# 10-ZYNQ_PWR_GND.net
KiCad netlist of a schematic drawn in Altium Designer
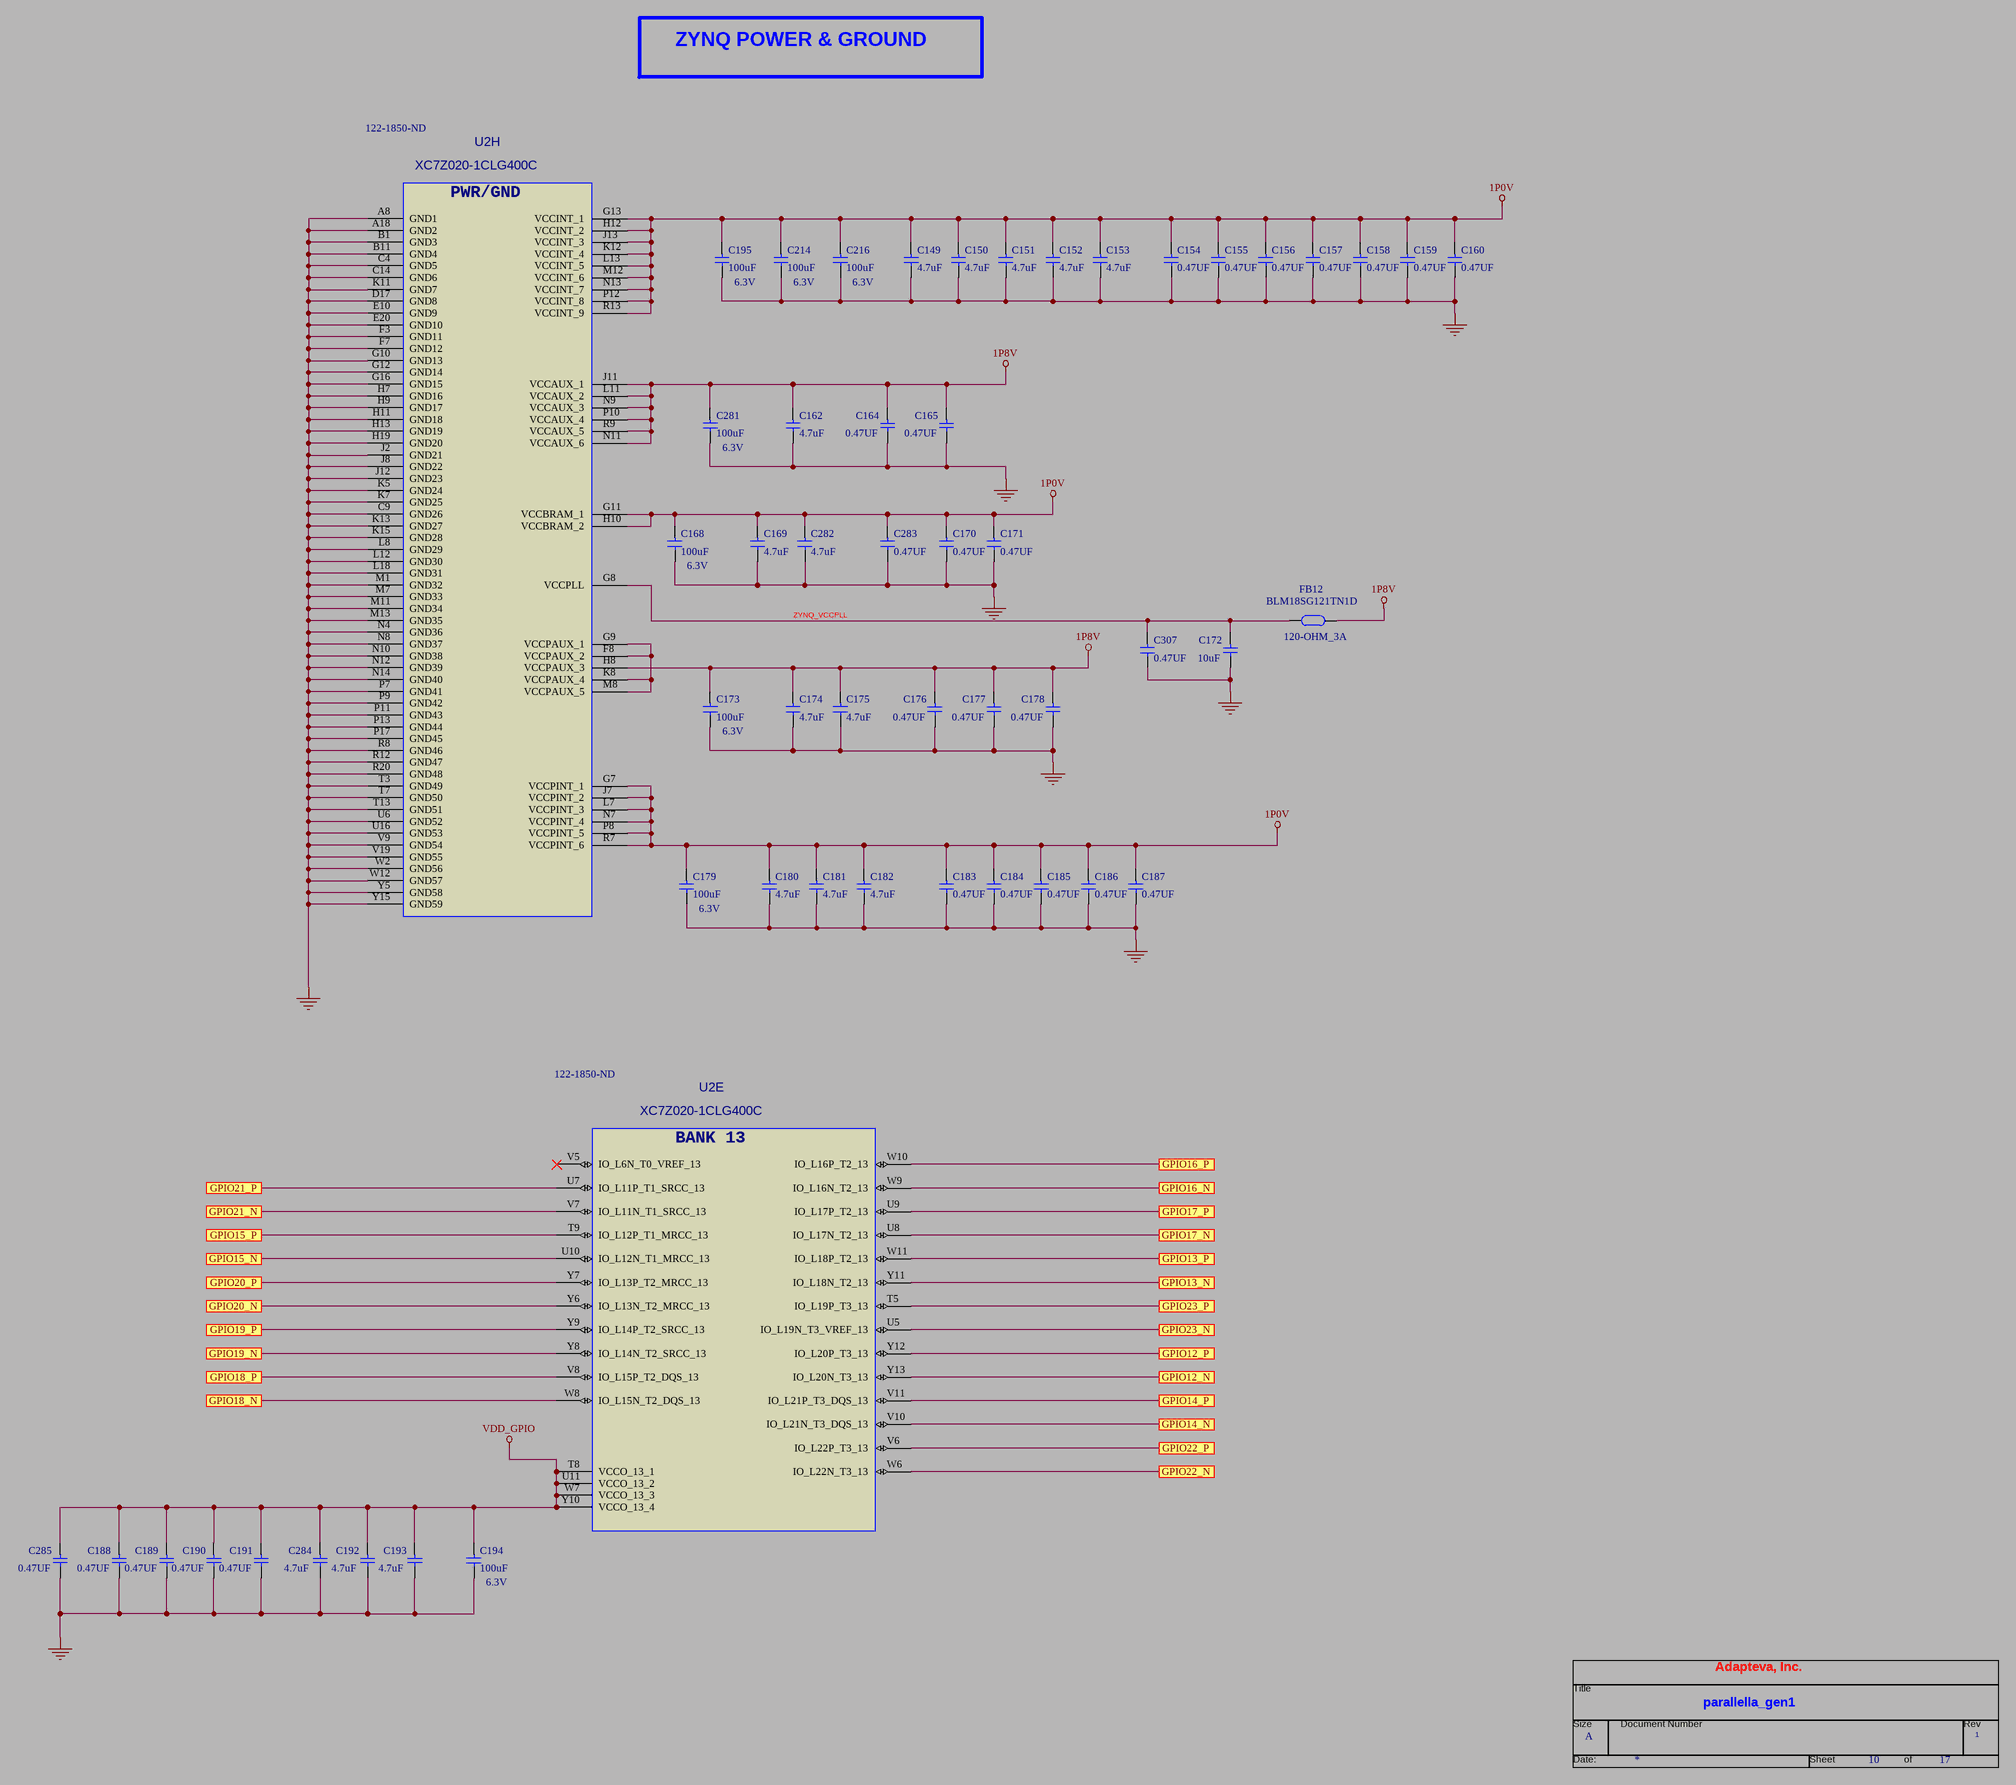
[diagram p0: 10-ZYNQ PWR & GND.SchDoc]

(export (version "E")
  (design (tool "Eeschema 10.0.6"))
  (components
    (comp (ref "C149")
      (value "4.7uF")
      (footprint "C0402")
      (description "CAP, 0402, 4.7UF, X5R, 6.3V")
      (fields (field (name "MFG PART NO") "C1005X5R0J475K") (field (name "MFG") "TDK"))
      (libsource (lib "*") (part "CAP0402_4P7UF_X5R"))
    )
    (comp (ref "C150")
      (value "4.7uF")
      (footprint "C0402")
      (description "CAP, 0402, 4.7UF, X5R, 6.3V")
      (fields (field (name "MFG PART NO") "C1005X5R0J475K") (field (name "MFG") "TDK"))
      (libsource (lib "*") (part "CAP0402_4P7UF_X5R"))
    )
    (comp (ref "C151")
      (value "4.7uF")
      (footprint "C0402")
      (description "CAP, 0402, 4.7UF, X5R, 6.3V")
      (fields (field (name "MFG PART NO") "C1005X5R0J475K") (field (name "MFG") "TDK"))
      (libsource (lib "*") (part "CAP0402_4P7UF_X5R"))
    )
    (comp (ref "C152")
      (value "4.7uF")
      (footprint "C0402")
      (description "CAP, 0402, 4.7UF, X5R, 6.3V")
      (fields (field (name "MFG PART NO") "C1005X5R0J475K") (field (name "MFG") "TDK"))
      (libsource (lib "*") (part "CAP0402_4P7UF_X5R"))
    )
    (comp (ref "C153")
      (value "4.7uF")
      (footprint "C0402")
      (description "CAP, 0402, 4.7UF, X5R, 6.3V")
      (fields (field (name "MFG PART NO") "C1005X5R0J475K") (field (name "MFG") "TDK"))
      (libsource (lib "*") (part "CAP0402_4P7UF_X5R"))
    )
    (comp (ref "C154")
      (value "0.47UF")
      (footprint "C0402")
      (description "CAP, 0402, 0.47UF, X5R, 16V")
      (fields (field (name "MFG") "TDK") (field (name "MFG PART NO") "C1005X5R1C474K"))
      (libsource (lib "*") (part "CAP0402_0P47UF_X5R"))
    )
    (comp (ref "C155")
      (value "0.47UF")
      (footprint "C0402")
      (description "CAP, 0402, 0.47UF, X5R, 16V")
      (fields (field (name "MFG") "TDK") (field (name "MFG PART NO") "C1005X5R1C474K"))
      (libsource (lib "*") (part "CAP0402_0P47UF_X5R"))
    )
    (comp (ref "C156")
      (value "0.47UF")
      (footprint "C0402")
      (description "CAP, 0402, 0.47UF, X5R, 16V")
      (fields (field (name "MFG") "TDK") (field (name "MFG PART NO") "C1005X5R1C474K"))
      (libsource (lib "*") (part "CAP0402_0P47UF_X5R"))
    )
    (comp (ref "C157")
      (value "0.47UF")
      (footprint "C0402")
      (description "CAP, 0402, 0.47UF, X5R, 16V")
      (fields (field (name "MFG") "TDK") (field (name "MFG PART NO") "C1005X5R1C474K"))
      (libsource (lib "*") (part "CAP0402_0P47UF_X5R"))
    )
    (comp (ref "C158")
      (value "0.47UF")
      (footprint "C0402")
      (description "CAP, 0402, 0.47UF, X5R, 16V")
      (fields (field (name "MFG") "TDK") (field (name "MFG PART NO") "C1005X5R1C474K"))
      (libsource (lib "*") (part "CAP0402_0P47UF_X5R"))
    )
    (comp (ref "C159")
      (value "0.47UF")
      (footprint "C0402")
      (description "CAP, 0402, 0.47UF, X5R, 16V")
      (fields (field (name "MFG") "TDK") (field (name "MFG PART NO") "C1005X5R1C474K"))
      (libsource (lib "*") (part "CAP0402_0P47UF_X5R"))
    )
    (comp (ref "C160")
      (value "0.47UF")
      (footprint "C0402")
      (description "CAP, 0402, 0.47UF, X5R, 16V")
      (fields (field (name "MFG") "TDK") (field (name "MFG PART NO") "C1005X5R1C474K"))
      (libsource (lib "*") (part "CAP0402_0P47UF_X5R"))
    )
    (comp (ref "C162")
      (value "4.7uF")
      (footprint "C0402")
      (description "CAP, 0402, 4.7UF, X5R, 6.3V")
      (fields (field (name "MFG PART NO") "C1005X5R0J475K") (field (name "MFG") "TDK"))
      (libsource (lib "*") (part "CAP0402_4P7UF_X5R"))
    )
    (comp (ref "C164")
      (value "0.47UF")
      (footprint "C0402")
      (description "CAP, 0402, 0.47UF, X5R, 16V")
      (fields (field (name "MFG") "TDK") (field (name "MFG PART NO") "C1005X5R1C474K"))
      (libsource (lib "*") (part "CAP0402_0P47UF_X5R"))
    )
    (comp (ref "C165")
      (value "0.47UF")
      (footprint "C0402")
      (description "CAP, 0402, 0.47UF, X5R, 16V")
      (fields (field (name "MFG") "TDK") (field (name "MFG PART NO") "C1005X5R1C474K"))
      (libsource (lib "*") (part "CAP0402_0P47UF_X5R"))
    )
    (comp (ref "C168")
      (value "100uF")
      (footprint "C1210")
      (description "CAP, 1210, 100UF, X5R, 6.3V, LOW ESR")
      (fields
        (field (name "VOLTAGE") "6.3V")
        (field (name "MFG PART NO") "GRM32ER60J107ME20L")
        (field (name "MFG") "MURATA")
      )
      (libsource (lib "*") (part "CAP1210_100UF_X5R_LOESR"))
    )
    (comp (ref "C169")
      (value "4.7uF")
      (footprint "C0402")
      (description "CAP, 0402, 4.7UF, X5R, 6.3V")
      (fields (field (name "MFG PART NO") "C1005X5R0J475K") (field (name "MFG") "TDK"))
      (libsource (lib "*") (part "CAP0402_4P7UF_X5R"))
    )
    (comp (ref "C170")
      (value "0.47UF")
      (footprint "C0402")
      (description "CAP, 0402, 0.47UF, X5R, 16V")
      (fields (field (name "MFG") "TDK") (field (name "MFG PART NO") "C1005X5R1C474K"))
      (libsource (lib "*") (part "CAP0402_0P47UF_X5R"))
    )
    (comp (ref "C171")
      (value "0.47UF")
      (footprint "C0402")
      (description "CAP, 0402, 0.47UF, X5R, 16V")
      (fields (field (name "MFG") "TDK") (field (name "MFG PART NO") "C1005X5R1C474K"))
      (libsource (lib "*") (part "CAP0402_0P47UF_X5R"))
    )
    (comp (ref "C172")
      (value "10uF")
      (footprint "C0603")
      (description "CAP, 0603, 10UF, X5R, 10V")
      (fields (field (name "MFG") "TAIYO YUDEN") (field (name "MFG PART NO") "LMK107BJ106MALTD"))
      (libsource (lib "*") (part "CAP0603_10UF_X5R"))
    )
    (comp (ref "C173")
      (value "100uF")
      (footprint "C1210")
      (description "CAP, 1210, 100UF, X5R, 6.3V, LOW ESR")
      (fields
        (field (name "VOLTAGE") "6.3V")
        (field (name "MFG PART NO") "GRM32ER60J107ME20L")
        (field (name "MFG") "MURATA")
      )
      (libsource (lib "*") (part "CAP1210_100UF_X5R_LOESR"))
    )
    (comp (ref "C174")
      (value "4.7uF")
      (footprint "C0402")
      (description "CAP, 0402, 4.7UF, X5R, 6.3V")
      (fields (field (name "MFG PART NO") "C1005X5R0J475K") (field (name "MFG") "TDK"))
      (libsource (lib "*") (part "CAP0402_4P7UF_X5R"))
    )
    (comp (ref "C175")
      (value "4.7uF")
      (footprint "C0402")
      (description "CAP, 0402, 4.7UF, X5R, 6.3V")
      (fields (field (name "MFG PART NO") "C1005X5R0J475K") (field (name "MFG") "TDK"))
      (libsource (lib "*") (part "CAP0402_4P7UF_X5R"))
    )
    (comp (ref "C176")
      (value "0.47UF")
      (footprint "C0402")
      (description "CAP, 0402, 0.47UF, X5R, 16V")
      (fields (field (name "MFG") "TDK") (field (name "MFG PART NO") "C1005X5R1C474K"))
      (libsource (lib "*") (part "CAP0402_0P47UF_X5R"))
    )
    (comp (ref "C177")
      (value "0.47UF")
      (footprint "C0402")
      (description "CAP, 0402, 0.47UF, X5R, 16V")
      (fields (field (name "MFG") "TDK") (field (name "MFG PART NO") "C1005X5R1C474K"))
      (libsource (lib "*") (part "CAP0402_0P47UF_X5R"))
    )
    (comp (ref "C178")
      (value "0.47UF")
      (footprint "C0402")
      (description "CAP, 0402, 0.47UF, X5R, 16V")
      (fields (field (name "MFG") "TDK") (field (name "MFG PART NO") "C1005X5R1C474K"))
      (libsource (lib "*") (part "CAP0402_0P47UF_X5R"))
    )
    (comp (ref "C179")
      (value "100uF")
      (footprint "C1210")
      (description "CAP, 1210, 100UF, X5R, 6.3V, LOW ESR")
      (fields
        (field (name "VOLTAGE") "6.3V")
        (field (name "MFG PART NO") "GRM32ER60J107ME20L")
        (field (name "MFG") "MURATA")
      )
      (libsource (lib "*") (part "CAP1210_100UF_X5R_LOESR"))
    )
    (comp (ref "C180")
      (value "4.7uF")
      (footprint "C0402")
      (description "CAP, 0402, 4.7UF, X5R, 6.3V")
      (fields (field (name "MFG PART NO") "C1005X5R0J475K") (field (name "MFG") "TDK"))
      (libsource (lib "*") (part "CAP0402_4P7UF_X5R"))
    )
    (comp (ref "C181")
      (value "4.7uF")
      (footprint "C0402")
      (description "CAP, 0402, 4.7UF, X5R, 6.3V")
      (fields (field (name "MFG PART NO") "C1005X5R0J475K") (field (name "MFG") "TDK"))
      (libsource (lib "*") (part "CAP0402_4P7UF_X5R"))
    )
    (comp (ref "C182")
      (value "4.7uF")
      (footprint "C0402")
      (description "CAP, 0402, 4.7UF, X5R, 6.3V")
      (fields (field (name "MFG PART NO") "C1005X5R0J475K") (field (name "MFG") "TDK"))
      (libsource (lib "*") (part "CAP0402_4P7UF_X5R"))
    )
    (comp (ref "C183")
      (value "0.47UF")
      (footprint "C0402")
      (description "CAP, 0402, 0.47UF, X5R, 16V")
      (fields (field (name "MFG") "TDK") (field (name "MFG PART NO") "C1005X5R1C474K"))
      (libsource (lib "*") (part "CAP0402_0P47UF_X5R"))
    )
    (comp (ref "C184")
      (value "0.47UF")
      (footprint "C0402")
      (description "CAP, 0402, 0.47UF, X5R, 16V")
      (fields (field (name "MFG") "TDK") (field (name "MFG PART NO") "C1005X5R1C474K"))
      (libsource (lib "*") (part "CAP0402_0P47UF_X5R"))
    )
    (comp (ref "C185")
      (value "0.47UF")
      (footprint "C0402")
      (description "CAP, 0402, 0.47UF, X5R, 16V")
      (fields (field (name "MFG") "TDK") (field (name "MFG PART NO") "C1005X5R1C474K"))
      (libsource (lib "*") (part "CAP0402_0P47UF_X5R"))
    )
    (comp (ref "C186")
      (value "0.47UF")
      (footprint "C0402")
      (description "CAP, 0402, 0.47UF, X5R, 16V")
      (fields (field (name "MFG") "TDK") (field (name "MFG PART NO") "C1005X5R1C474K"))
      (libsource (lib "*") (part "CAP0402_0P47UF_X5R"))
    )
    (comp (ref "C187")
      (value "0.47UF")
      (footprint "C0402")
      (description "CAP, 0402, 0.47UF, X5R, 16V")
      (fields (field (name "MFG") "TDK") (field (name "MFG PART NO") "C1005X5R1C474K"))
      (libsource (lib "*") (part "CAP0402_0P47UF_X5R"))
    )
    (comp (ref "C188")
      (value "0.47UF")
      (footprint "C0402")
      (description "CAP, 0402, 0.47UF, X5R, 16V")
      (fields (field (name "MFG") "TDK") (field (name "MFG PART NO") "C1005X5R1C474K"))
      (libsource (lib "*") (part "CAP0402_0P47UF_X5R"))
    )
    (comp (ref "C189")
      (value "0.47UF")
      (footprint "C0402")
      (description "CAP, 0402, 0.47UF, X5R, 16V")
      (fields (field (name "MFG") "TDK") (field (name "MFG PART NO") "C1005X5R1C474K"))
      (libsource (lib "*") (part "CAP0402_0P47UF_X5R"))
    )
    (comp (ref "C190")
      (value "0.47UF")
      (footprint "C0402")
      (description "CAP, 0402, 0.47UF, X5R, 16V")
      (fields (field (name "MFG") "TDK") (field (name "MFG PART NO") "C1005X5R1C474K"))
      (libsource (lib "*") (part "CAP0402_0P47UF_X5R"))
    )
    (comp (ref "C191")
      (value "0.47UF")
      (footprint "C0402")
      (description "CAP, 0402, 0.47UF, X5R, 16V")
      (fields (field (name "MFG") "TDK") (field (name "MFG PART NO") "C1005X5R1C474K"))
      (libsource (lib "*") (part "CAP0402_0P47UF_X5R"))
    )
    (comp (ref "C192")
      (value "4.7uF")
      (footprint "C0402")
      (description "CAP, 0402, 4.7UF, X5R, 6.3V")
      (fields (field (name "MFG PART NO") "C1005X5R0J475K") (field (name "MFG") "TDK"))
      (libsource (lib "*") (part "CAP0402_4P7UF_X5R"))
    )
    (comp (ref "C193")
      (value "4.7uF")
      (footprint "C0402")
      (description "CAP, 0402, 4.7UF, X5R, 6.3V")
      (fields (field (name "MFG PART NO") "C1005X5R0J475K") (field (name "MFG") "TDK"))
      (libsource (lib "*") (part "CAP0402_4P7UF_X5R"))
    )
    (comp (ref "C194")
      (value "100uF")
      (footprint "C1210")
      (description "CAP, 1210, 100UF, X5R, 6.3V, LOW ESR")
      (fields
        (field (name "VOLTAGE") "6.3V")
        (field (name "MFG PART NO") "GRM32ER60J107ME20L")
        (field (name "MFG") "MURATA")
      )
      (libsource (lib "*") (part "CAP1210_100UF_X5R_LOESR"))
    )
    (comp (ref "C195")
      (value "100uF")
      (footprint "C1210")
      (description "CAP, 1210, 100UF, X5R, 6.3V, LOW ESR")
      (fields
        (field (name "VOLTAGE") "6.3V")
        (field (name "MFG PART NO") "GRM32ER60J107ME20L")
        (field (name "MFG") "MURATA")
      )
      (libsource (lib "*") (part "CAP1210_100UF_X5R_LOESR"))
    )
    (comp (ref "C214")
      (value "100uF")
      (footprint "C1210")
      (description "CAP, 1210, 100UF, X5R, 6.3V, LOW ESR")
      (fields
        (field (name "VOLTAGE") "6.3V")
        (field (name "MFG PART NO") "GRM32ER60J107ME20L")
        (field (name "MFG") "MURATA")
      )
      (libsource (lib "*") (part "CAP1210_100UF_X5R_LOESR"))
    )
    (comp (ref "C216")
      (value "100uF")
      (footprint "C1210")
      (description "CAP, 1210, 100UF, X5R, 6.3V, LOW ESR")
      (fields
        (field (name "VOLTAGE") "6.3V")
        (field (name "MFG PART NO") "GRM32ER60J107ME20L")
        (field (name "MFG") "MURATA")
      )
      (libsource (lib "*") (part "CAP1210_100UF_X5R_LOESR"))
    )
    (comp (ref "C281")
      (value "100uF")
      (footprint "C1210")
      (description "CAP, 1210, 100UF, X5R, 6.3V, LOW ESR")
      (fields
        (field (name "VOLTAGE") "6.3V")
        (field (name "MFG PART NO") "GRM32ER60J107ME20L")
        (field (name "MFG") "MURATA")
      )
      (libsource (lib "*") (part "CAP1210_100UF_X5R_LOESR"))
    )
    (comp (ref "C282")
      (value "4.7uF")
      (footprint "C0402")
      (description "CAP, 0402, 4.7UF, X5R, 6.3V")
      (fields (field (name "MFG PART NO") "C1005X5R0J475K") (field (name "MFG") "TDK"))
      (libsource (lib "*") (part "CAP0402_4P7UF_X5R"))
    )
    (comp (ref "C283")
      (value "0.47UF")
      (footprint "C0402")
      (description "CAP, 0402, 0.47UF, X5R, 16V")
      (fields (field (name "MFG") "TDK") (field (name "MFG PART NO") "C1005X5R1C474K"))
      (libsource (lib "*") (part "CAP0402_0P47UF_X5R"))
    )
    (comp (ref "C284")
      (value "4.7uF")
      (footprint "C0402")
      (description "CAP, 0402, 4.7UF, X5R, 6.3V")
      (fields (field (name "MFG PART NO") "C1005X5R0J475K") (field (name "MFG") "TDK"))
      (libsource (lib "*") (part "CAP0402_4P7UF_X5R"))
    )
    (comp (ref "C285")
      (value "0.47UF")
      (footprint "C0402")
      (description "CAP, 0402, 0.47UF, X5R, 16V")
      (fields (field (name "MFG") "TDK") (field (name "MFG PART NO") "C1005X5R1C474K"))
      (libsource (lib "*") (part "CAP0402_0P47UF_X5R"))
    )
    (comp (ref "C307")
      (value "0.47UF")
      (footprint "C0402")
      (description "CAP, 0402, 0.47UF, X5R, 16V")
      (fields (field (name "MFG") "TDK") (field (name "MFG PART NO") "C1005X5R1C474K"))
      (libsource (lib "*") (part "CAP0402_0P47UF_X5R"))
    )
    (comp (ref "FB12")
      (value "120-OHM_3A")
      (footprint "BEAD_0603")
      (description "FERRITE, BEAD, FILTER, 0603, 3A")
      (fields (field (name "VENDOR PN") "BLM18SG121TN1D"))
      (libsource (lib "*") (part "BLM18SG121TN1D"))
    )
    (comp (ref "U2")
      (value "7Z020-CLG400")
      (footprint "CBGA400_17SQ_1P6H_P8MMP")
      (description "IC, EPP, XILINX, ZYNQ, 7Z020, CLG400")
      (fields
        (field (name "VENDOR PN") "XC7Z020-1CLG400C")
        (field (name "SUPPLIER PART NUMBER 1") "122-1850-ND")
      )
      (libsource (lib "*") (part "ZYNQ_7Z020_CLG400"))
    )
  )
  (nets
    (net (code "1") (name "/GPIO12_N") (class "Default")
      (node (ref "U2") (pin "Y13") (pinfunction "IO_L20N_T3_13_Y13") (pintype "bidirectional"))
    )
    (net (code "2") (name "/GPIO12_P") (class "Default")
      (node (ref "U2") (pin "Y12") (pinfunction "IO_L20P_T3_13_Y12") (pintype "bidirectional"))
    )
    (net (code "3") (name "/GPIO13_N") (class "Default")
      (node (ref "U2") (pin "Y11") (pinfunction "IO_L18N_T2_13_Y11") (pintype "bidirectional"))
    )
    (net (code "4") (name "/GPIO13_P") (class "Default")
      (node (ref "U2") (pin "W11") (pinfunction "IO_L18P_T2_13_W11") (pintype "bidirectional"))
    )
    (net (code "5") (name "/GPIO14_N") (class "Default")
      (node (ref "U2") (pin "V10") (pinfunction "IO_L21N_T3_DQS_13_V10") (pintype "bidirectional"))
    )
    (net (code "6") (name "/GPIO14_P") (class "Default")
      (node (ref "U2") (pin "V11") (pinfunction "IO_L21P_T3_DQS_13_V11") (pintype "bidirectional"))
    )
    (net (code "7") (name "/GPIO15_N") (class "Default")
      (node (ref "U2") (pin "U10") (pinfunction "IO_L12N_T1_MRCC_13_U10") (pintype "bidirectional"))
    )
    (net (code "8") (name "/GPIO15_P") (class "Default")
      (node (ref "U2") (pin "T9") (pinfunction "IO_L12P_T1_MRCC_13_T9") (pintype "bidirectional"))
    )
    (net (code "9") (name "/GPIO16_N") (class "Default")
      (node (ref "U2") (pin "W9") (pinfunction "IO_L16N_T2_13_W9") (pintype "bidirectional"))
    )
    (net (code "10") (name "/GPIO16_P") (class "Default")
      (node (ref "U2") (pin "W10") (pinfunction "IO_L16P_T2_13_W10") (pintype "bidirectional"))
    )
    (net (code "11") (name "/GPIO17_N") (class "Default")
      (node (ref "U2") (pin "U8") (pinfunction "IO_L17N_T2_13_U8") (pintype "bidirectional"))
    )
    (net (code "12") (name "/GPIO17_P") (class "Default")
      (node (ref "U2") (pin "U9") (pinfunction "IO_L17P_T2_13_U9") (pintype "bidirectional"))
    )
    (net (code "13") (name "/GPIO18_N") (class "Default")
      (node (ref "U2") (pin "W8") (pinfunction "IO_L15N_T2_DQS_13_W8") (pintype "bidirectional"))
    )
    (net (code "14") (name "/GPIO18_P") (class "Default")
      (node (ref "U2") (pin "V8") (pinfunction "IO_L15P_T2_DQS_13_V8") (pintype "bidirectional"))
    )
    (net (code "15") (name "/GPIO19_N") (class "Default")
      (node (ref "U2") (pin "Y8") (pinfunction "IO_L14N_T2_SRCC_13_Y8") (pintype "bidirectional"))
    )
    (net (code "16") (name "/GPIO19_P") (class "Default")
      (node (ref "U2") (pin "Y9") (pinfunction "IO_L14P_T2_SRCC_13_Y9") (pintype "bidirectional"))
    )
    (net (code "17") (name "/GPIO20_N") (class "Default")
      (node (ref "U2") (pin "Y6") (pinfunction "IO_L13N_T2_MRCC_13_Y6") (pintype "bidirectional"))
    )
    (net (code "18") (name "/GPIO20_P") (class "Default")
      (node (ref "U2") (pin "Y7") (pinfunction "IO_L13P_T2_MRCC_13_Y7") (pintype "bidirectional"))
    )
    (net (code "19") (name "/GPIO21_N") (class "Default")
      (node (ref "U2") (pin "V7") (pinfunction "IO_L11N_T1_SRCC_13_V7") (pintype "bidirectional"))
    )
    (net (code "20") (name "/GPIO21_P") (class "Default")
      (node (ref "U2") (pin "U7") (pinfunction "IO_L11P_T1_SRCC_13_U7") (pintype "bidirectional"))
    )
    (net (code "21") (name "/GPIO22_N") (class "Default")
      (node (ref "U2") (pin "W6") (pinfunction "IO_L22N_T3_13_W6") (pintype "bidirectional"))
    )
    (net (code "22") (name "/GPIO22_P") (class "Default")
      (node (ref "U2") (pin "V6") (pinfunction "IO_L22P_T3_13_V6") (pintype "bidirectional"))
    )
    (net (code "23") (name "/GPIO23_N") (class "Default")
      (node (ref "U2") (pin "U5") (pinfunction "IO_L19N_T3_VREF_13_U5") (pintype "bidirectional"))
    )
    (net (code "24") (name "/GPIO23_P") (class "Default")
      (node (ref "U2") (pin "T5") (pinfunction "IO_L19P_T3_13_T5") (pintype "bidirectional"))
    )
    (net (code "25") (name "/ZYNQ_VCCPLL") (class "Default")
      (node (ref "C172") (pin "1") (pinfunction "1_1") (pintype "passive"))
      (node (ref "C307") (pin "1") (pinfunction "1_1") (pintype "passive"))
      (node (ref "FB12") (pin "2") (pinfunction "2_2") (pintype "passive"))
      (node (ref "U2") (pin "G8") (pinfunction "VCCPLL_G8") (pintype "power_in"))
    )
    (net (code "26") (name "1P0V") (class "Default")
      (node (ref "C149") (pin "1") (pinfunction "1_1") (pintype "passive"))
      (node (ref "C150") (pin "1") (pinfunction "1_1") (pintype "passive"))
      (node (ref "C151") (pin "1") (pinfunction "1_1") (pintype "passive"))
      (node (ref "C152") (pin "1") (pinfunction "1_1") (pintype "passive"))
      (node (ref "C153") (pin "1") (pinfunction "1_1") (pintype "passive"))
      (node (ref "C154") (pin "1") (pinfunction "1_1") (pintype "passive"))
      (node (ref "C155") (pin "1") (pinfunction "1_1") (pintype "passive"))
      (node (ref "C156") (pin "1") (pinfunction "1_1") (pintype "passive"))
      (node (ref "C157") (pin "1") (pinfunction "1_1") (pintype "passive"))
      (node (ref "C158") (pin "1") (pinfunction "1_1") (pintype "passive"))
      (node (ref "C159") (pin "1") (pinfunction "1_1") (pintype "passive"))
      (node (ref "C160") (pin "1") (pinfunction "1_1") (pintype "passive"))
      (node (ref "C168") (pin "1") (pinfunction "1_1") (pintype "passive"))
      (node (ref "C169") (pin "1") (pinfunction "1_1") (pintype "passive"))
      (node (ref "C170") (pin "1") (pinfunction "1_1") (pintype "passive"))
      (node (ref "C171") (pin "1") (pinfunction "1_1") (pintype "passive"))
      (node (ref "C179") (pin "1") (pinfunction "1_1") (pintype "passive"))
      (node (ref "C180") (pin "1") (pinfunction "1_1") (pintype "passive"))
      (node (ref "C181") (pin "1") (pinfunction "1_1") (pintype "passive"))
      (node (ref "C182") (pin "1") (pinfunction "1_1") (pintype "passive"))
      (node (ref "C183") (pin "1") (pinfunction "1_1") (pintype "passive"))
      (node (ref "C184") (pin "1") (pinfunction "1_1") (pintype "passive"))
      (node (ref "C185") (pin "1") (pinfunction "1_1") (pintype "passive"))
      (node (ref "C186") (pin "1") (pinfunction "1_1") (pintype "passive"))
      (node (ref "C187") (pin "1") (pinfunction "1_1") (pintype "passive"))
      (node (ref "C195") (pin "1") (pinfunction "1_1") (pintype "passive"))
      (node (ref "C214") (pin "1") (pinfunction "1_1") (pintype "passive"))
      (node (ref "C216") (pin "1") (pinfunction "1_1") (pintype "passive"))
      (node (ref "C282") (pin "1") (pinfunction "1_1") (pintype "passive"))
      (node (ref "C283") (pin "1") (pinfunction "1_1") (pintype "passive"))
      (node (ref "U2") (pin "G11") (pinfunction "VCCBRAM_1_G11") (pintype "power_in"))
      (node (ref "U2") (pin "G13") (pinfunction "VCCINT_1_G13") (pintype "power_in"))
      (node (ref "U2") (pin "G7") (pinfunction "VCCPINT_1_G7") (pintype "power_in"))
      (node (ref "U2") (pin "H10") (pinfunction "VCCBRAM_2_H10") (pintype "power_in"))
      (node (ref "U2") (pin "H12") (pinfunction "VCCINT_2_H12") (pintype "power_in"))
      (node (ref "U2") (pin "J13") (pinfunction "VCCINT_3_J13") (pintype "power_in"))
      (node (ref "U2") (pin "J7") (pinfunction "VCCPINT_2_J7") (pintype "power_in"))
      (node (ref "U2") (pin "K12") (pinfunction "VCCINT_4_K12") (pintype "power_in"))
      (node (ref "U2") (pin "L13") (pinfunction "VCCINT_5_L13") (pintype "power_in"))
      (node (ref "U2") (pin "L7") (pinfunction "VCCPINT_3_L7") (pintype "power_in"))
      (node (ref "U2") (pin "M12") (pinfunction "VCCINT_6_M12") (pintype "power_in"))
      (node (ref "U2") (pin "N13") (pinfunction "VCCINT_7_N13") (pintype "power_in"))
      (node (ref "U2") (pin "N7") (pinfunction "VCCPINT_4_N7") (pintype "power_in"))
      (node (ref "U2") (pin "P12") (pinfunction "VCCINT_8_P12") (pintype "power_in"))
      (node (ref "U2") (pin "P8") (pinfunction "VCCPINT_5_P8") (pintype "power_in"))
      (node (ref "U2") (pin "R13") (pinfunction "VCCINT_9_R13") (pintype "power_in"))
      (node (ref "U2") (pin "R7") (pinfunction "VCCPINT_6_R7") (pintype "power_in"))
    )
    (net (code "27") (name "1P8V") (class "Default")
      (node (ref "C162") (pin "1") (pinfunction "1_1") (pintype "passive"))
      (node (ref "C164") (pin "1") (pinfunction "1_1") (pintype "passive"))
      (node (ref "C165") (pin "1") (pinfunction "1_1") (pintype "passive"))
      (node (ref "C173") (pin "1") (pinfunction "1_1") (pintype "passive"))
      (node (ref "C174") (pin "1") (pinfunction "1_1") (pintype "passive"))
      (node (ref "C175") (pin "1") (pinfunction "1_1") (pintype "passive"))
      (node (ref "C176") (pin "1") (pinfunction "1_1") (pintype "passive"))
      (node (ref "C177") (pin "1") (pinfunction "1_1") (pintype "passive"))
      (node (ref "C178") (pin "1") (pinfunction "1_1") (pintype "passive"))
      (node (ref "C281") (pin "1") (pinfunction "1_1") (pintype "passive"))
      (node (ref "FB12") (pin "1") (pinfunction "1_1") (pintype "passive"))
      (node (ref "U2") (pin "H8") (pinfunction "VCCPAUX_3_H8") (pintype "power_in"))
      (node (ref "U2") (pin "J11") (pinfunction "VCCAUX_1_J11") (pintype "power_in"))
      (node (ref "U2") (pin "L11") (pinfunction "VCCAUX_2_L11") (pintype "power_in"))
      (node (ref "U2") (pin "N11") (pinfunction "VCCAUX_6_N11") (pintype "power_in"))
      (node (ref "U2") (pin "N9") (pinfunction "VCCAUX_3_N9") (pintype "power_in"))
      (node (ref "U2") (pin "P10") (pinfunction "VCCAUX_4_P10") (pintype "power_in"))
      (node (ref "U2") (pin "R9") (pinfunction "VCCAUX_5_R9") (pintype "power_in"))
    )
    (net (code "28") (name "GND") (class "Default")
      (node (ref "C149") (pin "2") (pinfunction "2_2") (pintype "passive"))
      (node (ref "C150") (pin "2") (pinfunction "2_2") (pintype "passive"))
      (node (ref "C151") (pin "2") (pinfunction "2_2") (pintype "passive"))
      (node (ref "C152") (pin "2") (pinfunction "2_2") (pintype "passive"))
      (node (ref "C153") (pin "2") (pinfunction "2_2") (pintype "passive"))
      (node (ref "C154") (pin "2") (pinfunction "2_2") (pintype "passive"))
      (node (ref "C155") (pin "2") (pinfunction "2_2") (pintype "passive"))
      (node (ref "C156") (pin "2") (pinfunction "2_2") (pintype "passive"))
      (node (ref "C157") (pin "2") (pinfunction "2_2") (pintype "passive"))
      (node (ref "C158") (pin "2") (pinfunction "2_2") (pintype "passive"))
      (node (ref "C159") (pin "2") (pinfunction "2_2") (pintype "passive"))
      (node (ref "C160") (pin "2") (pinfunction "2_2") (pintype "passive"))
      (node (ref "C162") (pin "2") (pinfunction "2_2") (pintype "passive"))
      (node (ref "C164") (pin "2") (pinfunction "2_2") (pintype "passive"))
      (node (ref "C165") (pin "2") (pinfunction "2_2") (pintype "passive"))
      (node (ref "C168") (pin "2") (pinfunction "2_2") (pintype "passive"))
      (node (ref "C169") (pin "2") (pinfunction "2_2") (pintype "passive"))
      (node (ref "C170") (pin "2") (pinfunction "2_2") (pintype "passive"))
      (node (ref "C171") (pin "2") (pinfunction "2_2") (pintype "passive"))
      (node (ref "C172") (pin "2") (pinfunction "2_2") (pintype "passive"))
      (node (ref "C173") (pin "2") (pinfunction "2_2") (pintype "passive"))
      (node (ref "C174") (pin "2") (pinfunction "2_2") (pintype "passive"))
      (node (ref "C175") (pin "2") (pinfunction "2_2") (pintype "passive"))
      (node (ref "C176") (pin "2") (pinfunction "2_2") (pintype "passive"))
      (node (ref "C177") (pin "2") (pinfunction "2_2") (pintype "passive"))
      (node (ref "C178") (pin "2") (pinfunction "2_2") (pintype "passive"))
      (node (ref "C179") (pin "2") (pinfunction "2_2") (pintype "passive"))
      (node (ref "C180") (pin "2") (pinfunction "2_2") (pintype "passive"))
      (node (ref "C181") (pin "2") (pinfunction "2_2") (pintype "passive"))
      (node (ref "C182") (pin "2") (pinfunction "2_2") (pintype "passive"))
      (node (ref "C183") (pin "2") (pinfunction "2_2") (pintype "passive"))
      (node (ref "C184") (pin "2") (pinfunction "2_2") (pintype "passive"))
      (node (ref "C185") (pin "2") (pinfunction "2_2") (pintype "passive"))
      (node (ref "C186") (pin "2") (pinfunction "2_2") (pintype "passive"))
      (node (ref "C187") (pin "2") (pinfunction "2_2") (pintype "passive"))
      (node (ref "C188") (pin "2") (pinfunction "2_2") (pintype "passive"))
      (node (ref "C189") (pin "2") (pinfunction "2_2") (pintype "passive"))
      (node (ref "C190") (pin "2") (pinfunction "2_2") (pintype "passive"))
      (node (ref "C191") (pin "2") (pinfunction "2_2") (pintype "passive"))
      (node (ref "C192") (pin "2") (pinfunction "2_2") (pintype "passive"))
      (node (ref "C193") (pin "2") (pinfunction "2_2") (pintype "passive"))
      (node (ref "C194") (pin "2") (pinfunction "2_2") (pintype "passive"))
      (node (ref "C195") (pin "2") (pinfunction "2_2") (pintype "passive"))
      (node (ref "C214") (pin "2") (pinfunction "2_2") (pintype "passive"))
      (node (ref "C216") (pin "2") (pinfunction "2_2") (pintype "passive"))
      (node (ref "C281") (pin "2") (pinfunction "2_2") (pintype "passive"))
      (node (ref "C282") (pin "2") (pinfunction "2_2") (pintype "passive"))
      (node (ref "C283") (pin "2") (pinfunction "2_2") (pintype "passive"))
      (node (ref "C284") (pin "2") (pinfunction "2_2") (pintype "passive"))
      (node (ref "C285") (pin "2") (pinfunction "2_2") (pintype "passive"))
      (node (ref "C307") (pin "2") (pinfunction "2_2") (pintype "passive"))
      (node (ref "U2") (pin "A18") (pinfunction "GND2_A18") (pintype "power_in"))
      (node (ref "U2") (pin "A8") (pinfunction "GND1_A8") (pintype "power_in"))
      (node (ref "U2") (pin "B1") (pinfunction "GND3_B1") (pintype "power_in"))
      (node (ref "U2") (pin "B11") (pinfunction "GND4_B11") (pintype "power_in"))
      (node (ref "U2") (pin "C14") (pinfunction "GND6_C14") (pintype "power_in"))
      (node (ref "U2") (pin "C4") (pinfunction "GND5_C4") (pintype "power_in"))
      (node (ref "U2") (pin "C9") (pinfunction "GND26_C9") (pintype "power_in"))
      (node (ref "U2") (pin "D17") (pinfunction "GND8_D17") (pintype "power_in"))
      (node (ref "U2") (pin "E10") (pinfunction "GND9_E10") (pintype "power_in"))
      (node (ref "U2") (pin "E20") (pinfunction "GND10_E20") (pintype "power_in"))
      (node (ref "U2") (pin "F3") (pinfunction "GND11_F3") (pintype "power_in"))
      (node (ref "U2") (pin "F7") (pinfunction "GND12_F7") (pintype "power_in"))
      (node (ref "U2") (pin "G10") (pinfunction "GND13_G10") (pintype "power_in"))
      (node (ref "U2") (pin "G12") (pinfunction "GND14_G12") (pintype "power_in"))
      (node (ref "U2") (pin "G16") (pinfunction "GND15_G16") (pintype "power_in"))
      (node (ref "U2") (pin "H11") (pinfunction "GND18_H11") (pintype "power_in"))
      (node (ref "U2") (pin "H13") (pinfunction "GND19_H13") (pintype "power_in"))
      (node (ref "U2") (pin "H19") (pinfunction "GND20_H19") (pintype "power_in"))
      (node (ref "U2") (pin "H7") (pinfunction "GND16_H7") (pintype "power_in"))
      (node (ref "U2") (pin "H9") (pinfunction "GND17_H9") (pintype "power_in"))
      (node (ref "U2") (pin "J12") (pinfunction "GND23_J12") (pintype "power_in"))
      (node (ref "U2") (pin "J2") (pinfunction "GND21_J2") (pintype "power_in"))
      (node (ref "U2") (pin "J8") (pinfunction "GND22_J8") (pintype "power_in"))
      (node (ref "U2") (pin "K11") (pinfunction "GND7_K11") (pintype "power_in"))
      (node (ref "U2") (pin "K13") (pinfunction "GND27_K13") (pintype "power_in"))
      (node (ref "U2") (pin "K15") (pinfunction "GND28_K15") (pintype "power_in"))
      (node (ref "U2") (pin "K5") (pinfunction "GND24_K5") (pintype "power_in"))
      (node (ref "U2") (pin "K7") (pinfunction "GND25_K7") (pintype "power_in"))
      (node (ref "U2") (pin "L12") (pinfunction "GND30_L12") (pintype "power_in"))
      (node (ref "U2") (pin "L18") (pinfunction "GND31_L18") (pintype "power_in"))
      (node (ref "U2") (pin "L8") (pinfunction "GND29_L8") (pintype "power_in"))
      (node (ref "U2") (pin "M1") (pinfunction "GND32_M1") (pintype "power_in"))
      (node (ref "U2") (pin "M11") (pinfunction "GND34_M11") (pintype "power_in"))
      (node (ref "U2") (pin "M13") (pinfunction "GND35_M13") (pintype "power_in"))
      (node (ref "U2") (pin "M7") (pinfunction "GND33_M7") (pintype "power_in"))
      (node (ref "U2") (pin "N10") (pinfunction "GND38_N10") (pintype "power_in"))
      (node (ref "U2") (pin "N12") (pinfunction "GND39_N12") (pintype "power_in"))
      (node (ref "U2") (pin "N14") (pinfunction "GND40_N14") (pintype "power_in"))
      (node (ref "U2") (pin "N4") (pinfunction "GND36_N4") (pintype "power_in"))
      (node (ref "U2") (pin "N8") (pinfunction "GND37_N8") (pintype "power_in"))
      (node (ref "U2") (pin "P11") (pinfunction "GND43_P11") (pintype "power_in"))
      (node (ref "U2") (pin "P13") (pinfunction "GND44_P13") (pintype "power_in"))
      (node (ref "U2") (pin "P17") (pinfunction "GND45_P17") (pintype "power_in"))
      (node (ref "U2") (pin "P7") (pinfunction "GND41_P7") (pintype "power_in"))
      (node (ref "U2") (pin "P9") (pinfunction "GND42_P9") (pintype "power_in"))
      (node (ref "U2") (pin "R12") (pinfunction "GND47_R12") (pintype "power_in"))
      (node (ref "U2") (pin "R20") (pinfunction "GND48_R20") (pintype "power_in"))
      (node (ref "U2") (pin "R8") (pinfunction "GND46_R8") (pintype "power_in"))
      (node (ref "U2") (pin "T13") (pinfunction "GND51_T13") (pintype "power_in"))
      (node (ref "U2") (pin "T3") (pinfunction "GND49_T3") (pintype "power_in"))
      (node (ref "U2") (pin "T7") (pinfunction "GND50_T7") (pintype "power_in"))
      (node (ref "U2") (pin "U16") (pinfunction "GND53_U16") (pintype "power_in"))
      (node (ref "U2") (pin "U6") (pinfunction "GND52_U6") (pintype "power_in"))
      (node (ref "U2") (pin "V19") (pinfunction "GND55_V19") (pintype "power_in"))
      (node (ref "U2") (pin "V9") (pinfunction "GND54_V9") (pintype "power_in"))
      (node (ref "U2") (pin "W12") (pinfunction "GND57_W12") (pintype "power_in"))
      (node (ref "U2") (pin "W2") (pinfunction "GND56_W2") (pintype "power_in"))
      (node (ref "U2") (pin "Y15") (pinfunction "GND59_Y15") (pintype "power_in"))
      (node (ref "U2") (pin "Y5") (pinfunction "GND58_Y5") (pintype "power_in"))
    )
    (net (code "29") (name "Net-(U2H-VCCPAUX_1)") (class "Default")
      (node (ref "U2") (pin "F8") (pinfunction "VCCPAUX_2_F8") (pintype "power_in"))
      (node (ref "U2") (pin "G9") (pinfunction "VCCPAUX_1_G9") (pintype "power_in"))
      (node (ref "U2") (pin "K8") (pinfunction "VCCPAUX_4_K8") (pintype "power_in"))
      (node (ref "U2") (pin "M8") (pinfunction "VCCPAUX_5_M8") (pintype "power_in"))
    )
    (net (code "30") (name "VDD_GPIO") (class "Default")
      (node (ref "C188") (pin "1") (pinfunction "1_1") (pintype "passive"))
      (node (ref "C189") (pin "1") (pinfunction "1_1") (pintype "passive"))
      (node (ref "C190") (pin "1") (pinfunction "1_1") (pintype "passive"))
      (node (ref "C191") (pin "1") (pinfunction "1_1") (pintype "passive"))
      (node (ref "C192") (pin "1") (pinfunction "1_1") (pintype "passive"))
      (node (ref "C193") (pin "1") (pinfunction "1_1") (pintype "passive"))
      (node (ref "C194") (pin "1") (pinfunction "1_1") (pintype "passive"))
      (node (ref "C284") (pin "1") (pinfunction "1_1") (pintype "passive"))
      (node (ref "C285") (pin "1") (pinfunction "1_1") (pintype "passive"))
      (node (ref "U2") (pin "T8") (pinfunction "VCCO_13_1_T8") (pintype "power_in"))
      (node (ref "U2") (pin "U11") (pinfunction "VCCO_13_2_U11") (pintype "power_in"))
      (node (ref "U2") (pin "W7") (pinfunction "VCCO_13_3_W7") (pintype "power_in"))
      (node (ref "U2") (pin "Y10") (pinfunction "VCCO_13_4_Y10") (pintype "power_in"))
    )
    (net (code "31") (name "unconnected-(U2E-IO_L6N_T0_VREF_13-PadV5)") (class "Default")
      (node (ref "U2") (pin "V5") (pinfunction "IO_L6N_T0_VREF_13_V5") (pintype "bidirectional+no_connect"))
    )
  )
)
